# vfd_controller_io.net
KiCad netlist of a schematic drawn in EAGLE
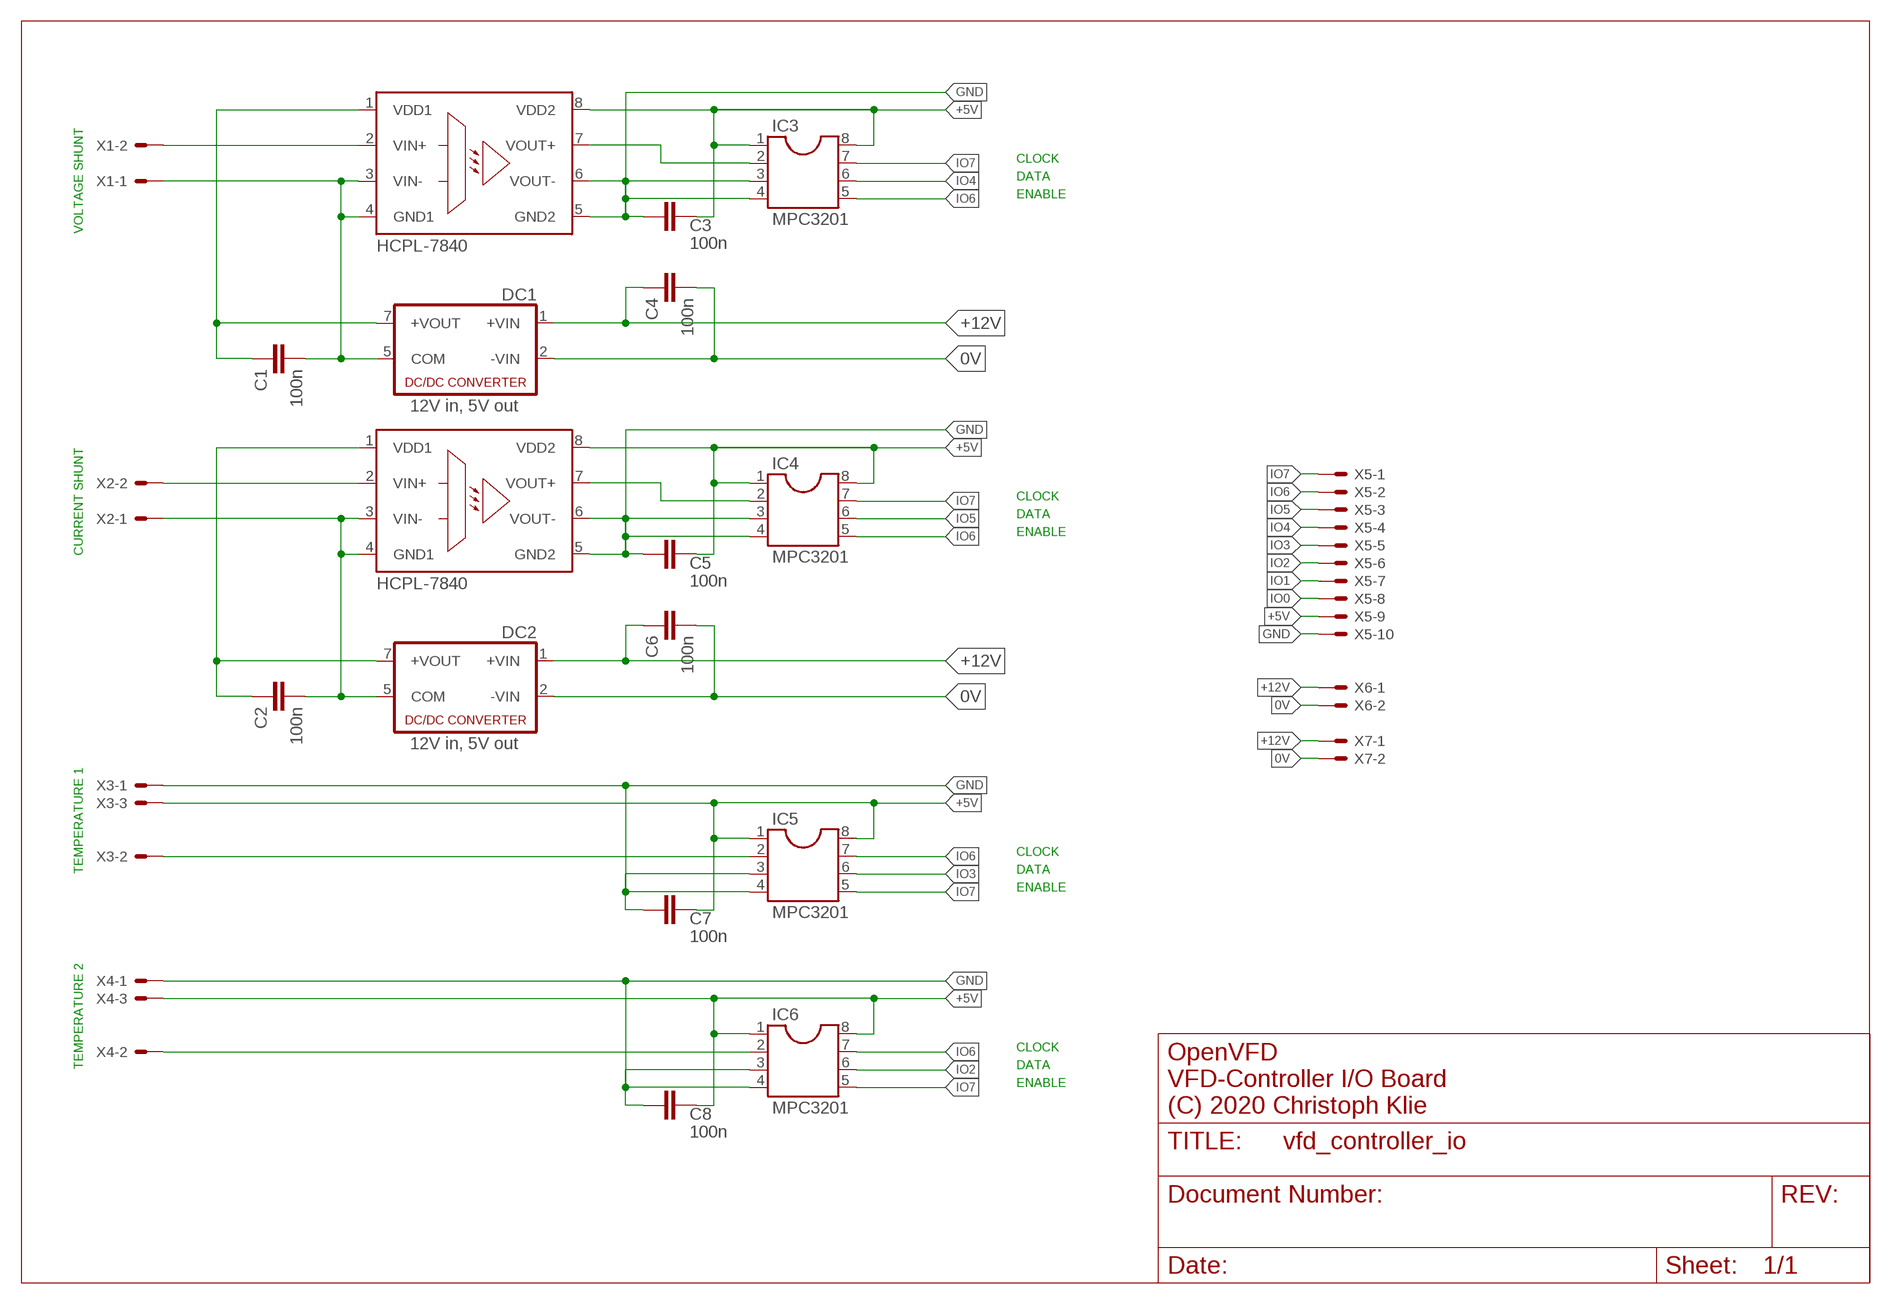
[diagram p0: schematic, sheet 1]

(export (version "E")
  (design (tool "Eeschema 10.0.6"))
  (components
    (comp (ref "C1")
      (value "100n")
      (footprint "eagle-import:C050-025X075")
      (libsource (lib "eagle-import") (part "C-EU050-025X075"))
    )
    (comp (ref "C2")
      (value "100n")
      (footprint "eagle-import:C050-025X075")
      (libsource (lib "eagle-import") (part "C-EU050-025X075"))
    )
    (comp (ref "C3")
      (value "100n")
      (footprint "eagle-import:C050-025X075")
      (libsource (lib "eagle-import") (part "C-EU050-025X075"))
    )
    (comp (ref "C4")
      (value "100n")
      (footprint "eagle-import:C025-024X044")
      (libsource (lib "eagle-import") (part "C-EU025-024X044"))
    )
    (comp (ref "C5")
      (value "100n")
      (footprint "eagle-import:C050-025X075")
      (libsource (lib "eagle-import") (part "C-EU050-025X075"))
    )
    (comp (ref "C6")
      (value "100n")
      (footprint "eagle-import:C025-024X044")
      (libsource (lib "eagle-import") (part "C-EU025-024X044"))
    )
    (comp (ref "C7")
      (value "100n")
      (footprint "eagle-import:C050-025X075")
      (libsource (lib "eagle-import") (part "C-EU050-025X075"))
    )
    (comp (ref "C8")
      (value "100n")
      (footprint "eagle-import:C050-025X075")
      (libsource (lib "eagle-import") (part "C-EU050-025X075"))
    )
    (comp (ref "DC1")
      (value "12V in, 5V out")
      (footprint "eagle-import:MEV")
      (libsource (lib "eagle-import") (part "MEV"))
    )
    (comp (ref "DC2")
      (value "12V in, 5V out")
      (footprint "eagle-import:MEV")
      (libsource (lib "eagle-import") (part "MEV"))
    )
    (comp (ref "IC1")
      (value "HCPL-7840")
      (footprint "eagle-import:DIL08")
      (fields (field (name "MPN") "HCPL-7800A#500"))
      (libsource (lib "eagle-import") (part "HCPL-7800"))
    )
    (comp (ref "IC2")
      (value "HCPL-7840")
      (footprint "eagle-import:DIL08")
      (fields (field (name "MPN") "HCPL-7800A#500"))
      (libsource (lib "eagle-import") (part "HCPL-7800"))
    )
    (comp (ref "IC3")
      (value "MPC3201")
      (footprint "eagle-import:DIL08")
      (libsource (lib "eagle-import") (part "DIL8"))
    )
    (comp (ref "IC4")
      (value "MPC3201")
      (footprint "eagle-import:DIL08")
      (libsource (lib "eagle-import") (part "DIL8"))
    )
    (comp (ref "IC5")
      (value "MPC3201")
      (footprint "eagle-import:DIL08")
      (libsource (lib "eagle-import") (part "DIL8"))
    )
    (comp (ref "IC6")
      (value "MPC3201")
      (footprint "eagle-import:DIL08")
      (libsource (lib "eagle-import") (part "DIL8"))
    )
    (comp (ref "X1")
      (value "JST-XH-02-PIN-LONG-PAD")
      (footprint "eagle-import:JST-XH-02-PACKAGE-LONG-PAD")
      (fields (field (name "R") "JST XH2P ST"))
      (libsource (lib "eagle-import") (part "JST-XH-02-PIN-LONG-PAD"))
    )
    (comp (ref "X2")
      (value "JST-XH-02-PIN-LONG-PAD")
      (footprint "eagle-import:JST-XH-02-PACKAGE-LONG-PAD")
      (fields (field (name "R") "JST XH2P ST"))
      (libsource (lib "eagle-import") (part "JST-XH-02-PIN-LONG-PAD"))
    )
    (comp (ref "X3")
      (value "JST-XH-03-PIN-LONG-PAD")
      (footprint "eagle-import:JST-XH-03-PACKAGE-LONG-PAD")
      (fields (field (name "R") "JST XH3P ST"))
      (libsource (lib "eagle-import") (part "JST-XH-03-PIN-LONG-PAD"))
    )
    (comp (ref "X4")
      (value "JST-XH-03-PIN-LONG-PAD")
      (footprint "eagle-import:JST-XH-03-PACKAGE-LONG-PAD")
      (fields (field (name "R") "JST XH3P ST"))
      (libsource (lib "eagle-import") (part "JST-XH-03-PIN-LONG-PAD"))
    )
    (comp (ref "X5")
      (value "JST-XH-10-PIN-LONG-PAD")
      (footprint "eagle-import:JST-XH-10-PACKAGE-LONG-PAD")
      (fields (field (name "R") "JST XH10P ST"))
      (libsource (lib "eagle-import") (part "JST-XH-10-PIN-LONG-PAD"))
    )
    (comp (ref "X6")
      (value "JST-XH-02-PIN-LONG-PAD")
      (footprint "eagle-import:JST-XH-02-PACKAGE-LONG-PAD")
      (fields (field (name "R") "JST XH2P ST"))
      (libsource (lib "eagle-import") (part "JST-XH-02-PIN-LONG-PAD"))
    )
    (comp (ref "X7")
      (value "JST-XH-02-PIN-LONG-PAD")
      (footprint "eagle-import:JST-XH-02-PACKAGE-LONG-PAD")
      (fields (field (name "R") "JST XH2P ST"))
      (libsource (lib "eagle-import") (part "JST-XH-02-PIN-LONG-PAD"))
    )
  )
  (nets
    (net (code "1") (name "+5V") (class "Default")
      (node (ref "C3") (pin "2") (pinfunction "2_2") (pintype "passive"))
      (node (ref "C5") (pin "2") (pinfunction "2_2") (pintype "passive"))
      (node (ref "C7") (pin "2") (pinfunction "2_2") (pintype "passive"))
      (node (ref "C8") (pin "2") (pinfunction "2_2") (pintype "passive"))
      (node (ref "IC1") (pin "8") (pinfunction "VDD2_8") (pintype "power_in"))
      (node (ref "IC2") (pin "8") (pinfunction "VDD2_8") (pintype "power_in"))
      (node (ref "IC3") (pin "1") (pinfunction "1_1") (pintype "passive"))
      (node (ref "IC3") (pin "8") (pinfunction "8_8") (pintype "passive"))
      (node (ref "IC4") (pin "1") (pinfunction "1_1") (pintype "passive"))
      (node (ref "IC4") (pin "8") (pinfunction "8_8") (pintype "passive"))
      (node (ref "IC5") (pin "1") (pinfunction "1_1") (pintype "passive"))
      (node (ref "IC5") (pin "8") (pinfunction "8_8") (pintype "passive"))
      (node (ref "IC6") (pin "1") (pinfunction "1_1") (pintype "passive"))
      (node (ref "IC6") (pin "8") (pinfunction "8_8") (pintype "passive"))
      (node (ref "X3") (pin "3") (pinfunction "S_3") (pintype "passive"))
      (node (ref "X4") (pin "3") (pinfunction "S_3") (pintype "passive"))
      (node (ref "X5") (pin "9") (pinfunction "S_9") (pintype "passive"))
    )
    (net (code "2") (name "+12V") (class "Default")
      (node (ref "C4") (pin "1") (pinfunction "1_1") (pintype "passive"))
      (node (ref "C6") (pin "1") (pinfunction "1_1") (pintype "passive"))
      (node (ref "DC1") (pin "1") (pinfunction "+VIN_1") (pintype "passive"))
      (node (ref "DC2") (pin "1") (pinfunction "+VIN_1") (pintype "passive"))
      (node (ref "X6") (pin "1") (pinfunction "S_1") (pintype "passive"))
      (node (ref "X7") (pin "1") (pinfunction "S_1") (pintype "passive"))
    )
    (net (code "3") (name "0V") (class "Default")
      (node (ref "C4") (pin "2") (pinfunction "2_2") (pintype "passive"))
      (node (ref "C6") (pin "2") (pinfunction "2_2") (pintype "passive"))
      (node (ref "DC1") (pin "2") (pinfunction "-VIN_2") (pintype "passive"))
      (node (ref "DC2") (pin "2") (pinfunction "-VIN_2") (pintype "passive"))
      (node (ref "X6") (pin "2") (pinfunction "S_2") (pintype "passive"))
      (node (ref "X7") (pin "2") (pinfunction "S_2") (pintype "passive"))
    )
    (net (code "4") (name "GND") (class "Default")
      (node (ref "C3") (pin "1") (pinfunction "1_1") (pintype "passive"))
      (node (ref "C5") (pin "1") (pinfunction "1_1") (pintype "passive"))
      (node (ref "C7") (pin "1") (pinfunction "1_1") (pintype "passive"))
      (node (ref "C8") (pin "1") (pinfunction "1_1") (pintype "passive"))
      (node (ref "IC1") (pin "5") (pinfunction "GND2_5") (pintype "power_in"))
      (node (ref "IC1") (pin "6") (pinfunction "VOUT-_6") (pintype "power_in"))
      (node (ref "IC2") (pin "5") (pinfunction "GND2_5") (pintype "power_in"))
      (node (ref "IC2") (pin "6") (pinfunction "VOUT-_6") (pintype "power_in"))
      (node (ref "IC3") (pin "3") (pinfunction "3_3") (pintype "passive"))
      (node (ref "IC3") (pin "4") (pinfunction "4_4") (pintype "passive"))
      (node (ref "IC4") (pin "3") (pinfunction "3_3") (pintype "passive"))
      (node (ref "IC4") (pin "4") (pinfunction "4_4") (pintype "passive"))
      (node (ref "IC5") (pin "3") (pinfunction "3_3") (pintype "passive"))
      (node (ref "IC5") (pin "4") (pinfunction "4_4") (pintype "passive"))
      (node (ref "IC6") (pin "3") (pinfunction "3_3") (pintype "passive"))
      (node (ref "IC6") (pin "4") (pinfunction "4_4") (pintype "passive"))
      (node (ref "X3") (pin "1") (pinfunction "S_1") (pintype "passive"))
      (node (ref "X4") (pin "1") (pinfunction "S_1") (pintype "passive"))
      (node (ref "X5") (pin "10") (pinfunction "S_10") (pintype "passive"))
    )
    (net (code "5") (name "IO0") (class "Default")
      (node (ref "X5") (pin "8") (pinfunction "S_8") (pintype "passive"))
    )
    (net (code "6") (name "IO1") (class "Default")
      (node (ref "X5") (pin "7") (pinfunction "S_7") (pintype "passive"))
    )
    (net (code "7") (name "IO2") (class "Default")
      (node (ref "IC6") (pin "6") (pinfunction "6_6") (pintype "passive"))
      (node (ref "X5") (pin "6") (pinfunction "S_6") (pintype "passive"))
    )
    (net (code "8") (name "IO3") (class "Default")
      (node (ref "IC5") (pin "6") (pinfunction "6_6") (pintype "passive"))
      (node (ref "X5") (pin "5") (pinfunction "S_5") (pintype "passive"))
    )
    (net (code "9") (name "IO4") (class "Default")
      (node (ref "IC3") (pin "6") (pinfunction "6_6") (pintype "passive"))
      (node (ref "X5") (pin "4") (pinfunction "S_4") (pintype "passive"))
    )
    (net (code "10") (name "IO5") (class "Default")
      (node (ref "IC4") (pin "6") (pinfunction "6_6") (pintype "passive"))
      (node (ref "X5") (pin "3") (pinfunction "S_3") (pintype "passive"))
    )
    (net (code "11") (name "IO6") (class "Default")
      (node (ref "IC3") (pin "5") (pinfunction "5_5") (pintype "passive"))
      (node (ref "IC4") (pin "5") (pinfunction "5_5") (pintype "passive"))
      (node (ref "IC5") (pin "7") (pinfunction "7_7") (pintype "passive"))
      (node (ref "IC6") (pin "7") (pinfunction "7_7") (pintype "passive"))
      (node (ref "X5") (pin "2") (pinfunction "S_2") (pintype "passive"))
    )
    (net (code "12") (name "IO7") (class "Default")
      (node (ref "IC3") (pin "7") (pinfunction "7_7") (pintype "passive"))
      (node (ref "IC4") (pin "7") (pinfunction "7_7") (pintype "passive"))
      (node (ref "IC5") (pin "5") (pinfunction "5_5") (pintype "passive"))
      (node (ref "IC6") (pin "5") (pinfunction "5_5") (pintype "passive"))
      (node (ref "X5") (pin "1") (pinfunction "S_1") (pintype "passive"))
    )
    (net (code "13") (name "Net-(DC1-+VOUT)") (class "Default")
      (node (ref "C1") (pin "1") (pinfunction "1_1") (pintype "passive"))
      (node (ref "DC1") (pin "7") (pinfunction "+VOUT_7") (pintype "passive"))
      (node (ref "IC1") (pin "1") (pinfunction "VDD1_1") (pintype "power_in"))
    )
    (net (code "14") (name "Net-(DC1-COM)") (class "Default")
      (node (ref "C1") (pin "2") (pinfunction "2_2") (pintype "passive"))
      (node (ref "DC1") (pin "5") (pinfunction "COM_5") (pintype "passive"))
      (node (ref "IC1") (pin "3") (pinfunction "VIN-_3") (pintype "power_in"))
      (node (ref "IC1") (pin "4") (pinfunction "GND1_4") (pintype "power_in"))
      (node (ref "X1") (pin "1") (pinfunction "S_1") (pintype "passive"))
    )
    (net (code "15") (name "Net-(DC2-+VOUT)") (class "Default")
      (node (ref "C2") (pin "1") (pinfunction "1_1") (pintype "passive"))
      (node (ref "DC2") (pin "7") (pinfunction "+VOUT_7") (pintype "passive"))
      (node (ref "IC2") (pin "1") (pinfunction "VDD1_1") (pintype "power_in"))
    )
    (net (code "16") (name "Net-(DC2-COM)") (class "Default")
      (node (ref "C2") (pin "2") (pinfunction "2_2") (pintype "passive"))
      (node (ref "DC2") (pin "5") (pinfunction "COM_5") (pintype "passive"))
      (node (ref "IC2") (pin "3") (pinfunction "VIN-_3") (pintype "power_in"))
      (node (ref "IC2") (pin "4") (pinfunction "GND1_4") (pintype "power_in"))
      (node (ref "X2") (pin "1") (pinfunction "S_1") (pintype "passive"))
    )
    (net (code "17") (name "Net-(IC1-VIN+)") (class "Default")
      (node (ref "IC1") (pin "2") (pinfunction "VIN+_2") (pintype "power_in"))
      (node (ref "X1") (pin "2") (pinfunction "S_2") (pintype "passive"))
    )
    (net (code "18") (name "Net-(IC1-VOUT+)") (class "Default")
      (node (ref "IC1") (pin "7") (pinfunction "VOUT+_7") (pintype "power_in"))
      (node (ref "IC3") (pin "2") (pinfunction "2_2") (pintype "passive"))
    )
    (net (code "19") (name "Net-(IC2-VIN+)") (class "Default")
      (node (ref "IC2") (pin "2") (pinfunction "VIN+_2") (pintype "power_in"))
      (node (ref "X2") (pin "2") (pinfunction "S_2") (pintype "passive"))
    )
    (net (code "20") (name "Net-(IC2-VOUT+)") (class "Default")
      (node (ref "IC2") (pin "7") (pinfunction "VOUT+_7") (pintype "power_in"))
      (node (ref "IC4") (pin "2") (pinfunction "2_2") (pintype "passive"))
    )
    (net (code "21") (name "Net-(X3B-S)") (class "Default")
      (node (ref "IC5") (pin "2") (pinfunction "2_2") (pintype "passive"))
      (node (ref "X3") (pin "2") (pinfunction "S_2") (pintype "passive"))
    )
    (net (code "22") (name "Net-(X4B-S)") (class "Default")
      (node (ref "IC6") (pin "2") (pinfunction "2_2") (pintype "passive"))
      (node (ref "X4") (pin "2") (pinfunction "S_2") (pintype "passive"))
    )
  )
)
